# M040X.net
KiCad netlist of a schematic drawn in EAGLE
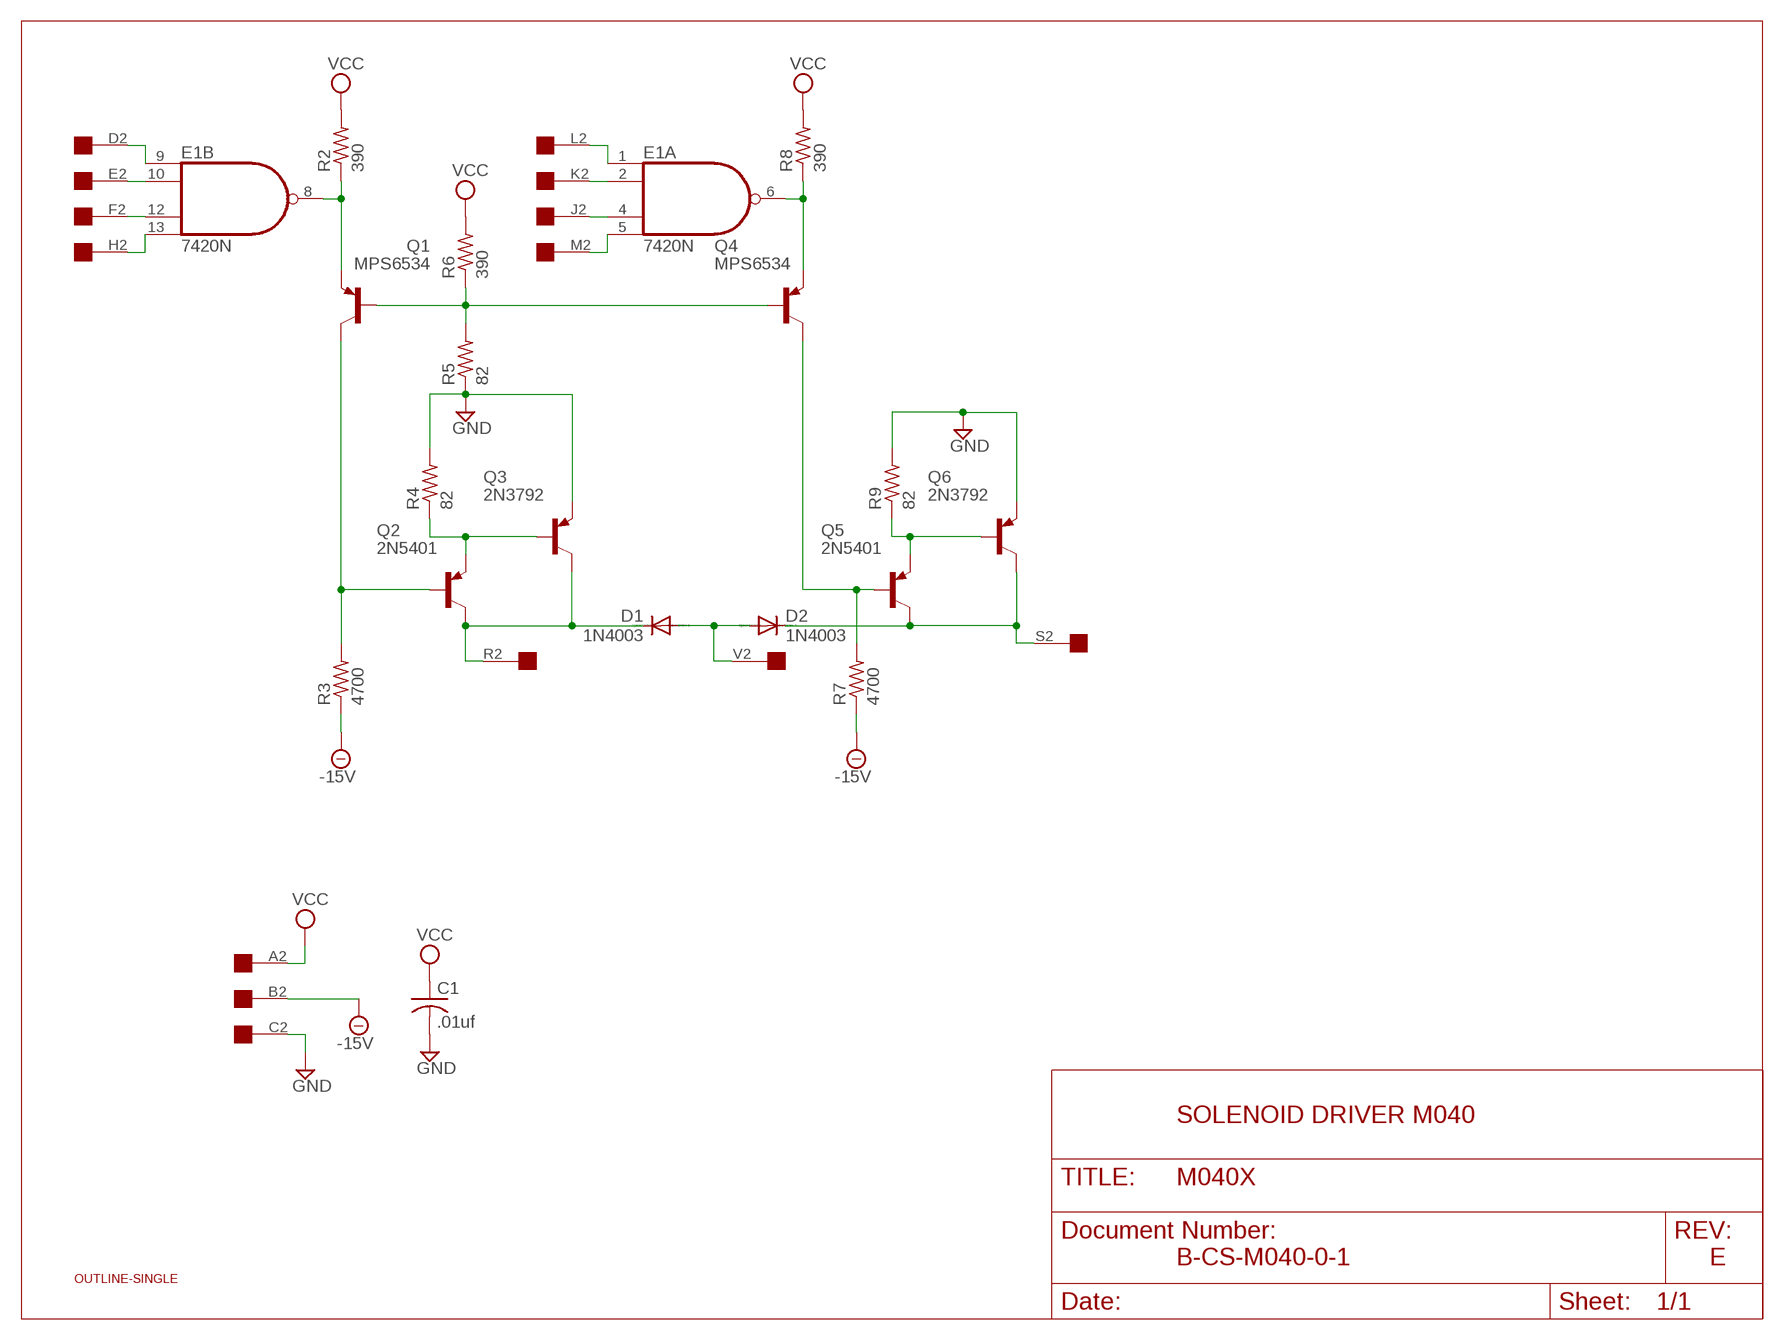
[diagram p0: schematic, sheet 1]

(export (version "E")
  (design (tool "Eeschema 10.0.6"))
  (components
    (comp (ref "C1")
      (value ".01uf")
      (footprint "eagle-import:C050-025X075")
      (libsource (lib "eagle-import") (part "C-US050-025X075"))
    )
    (comp (ref "D1")
      (value "1N4003")
      (footprint "eagle-import:DO41-10")
      (libsource (lib "eagle-import") (part "1N4004"))
    )
    (comp (ref "D2")
      (value "1N4003")
      (footprint "eagle-import:DO41-10")
      (libsource (lib "eagle-import") (part "1N4004"))
    )
    (comp (ref "E1")
      (value "7420N")
      (footprint "eagle-import:DIL14")
      (libsource (lib "eagle-import") (part "7420NS"))
    )
    (comp (ref "Q1")
      (value "MPS6534")
      (footprint "eagle-import:TO39")
      (libsource (lib "eagle-import") (part "-PNP-TO39-EBC2N2904"))
    )
    (comp (ref "Q2")
      (value "2N5401")
      (footprint "eagle-import:TO39")
      (libsource (lib "eagle-import") (part "-PNP-TO39-EBC2N2904"))
    )
    (comp (ref "Q3")
      (value "2N3792")
      (footprint "eagle-import:TO3")
      (libsource (lib "eagle-import") (part "-PNP-TO3"))
    )
    (comp (ref "Q4")
      (value "MPS6534")
      (footprint "eagle-import:TO39")
      (libsource (lib "eagle-import") (part "-PNP-TO39-EBC2N2904"))
    )
    (comp (ref "Q5")
      (value "2N5401")
      (footprint "eagle-import:TO39")
      (libsource (lib "eagle-import") (part "-PNP-TO39-EBC2N2904"))
    )
    (comp (ref "Q6")
      (value "2N3792")
      (footprint "eagle-import:TO3")
      (libsource (lib "eagle-import") (part "-PNP-TO3"))
    )
    (comp (ref "R2")
      (value "390")
      (footprint "eagle-import:0207_10")
      (libsource (lib "eagle-import") (part "R-US_0207/10"))
    )
    (comp (ref "R3")
      (value "4700")
      (footprint "eagle-import:0207_10")
      (libsource (lib "eagle-import") (part "R-US_0207/10"))
    )
    (comp (ref "R4")
      (value "82")
      (footprint "eagle-import:0207_10")
      (libsource (lib "eagle-import") (part "R-US_0207/10"))
    )
    (comp (ref "R5")
      (value "82")
      (footprint "eagle-import:0207_10")
      (libsource (lib "eagle-import") (part "R-US_0207/10"))
    )
    (comp (ref "R6")
      (value "390")
      (footprint "eagle-import:0207_10")
      (libsource (lib "eagle-import") (part "R-US_0207/10"))
    )
    (comp (ref "R7")
      (value "4700")
      (footprint "eagle-import:0207_10")
      (libsource (lib "eagle-import") (part "R-US_0207/10"))
    )
    (comp (ref "R8")
      (value "390")
      (footprint "eagle-import:0207_10")
      (libsource (lib "eagle-import") (part "R-US_0207/10"))
    )
    (comp (ref "R9")
      (value "82")
      (footprint "eagle-import:0207_10")
      (libsource (lib "eagle-import") (part "R-US_0207/10"))
    )
    (comp (ref "U$1")
      (value "OUTLINE-SINGLE")
      (footprint "eagle-import:SINGLE")
      (libsource (lib "eagle-import") (part "OUTLINE-SINGLE"))
    )
    (comp (ref "U$2")
      (value "EDGE-1")
      (footprint "eagle-import:EDGE-CON1")
      (libsource (lib "eagle-import") (part "EDGE-1"))
    )
  )
  (nets
    (net (code "1") (name "-15V") (class "Default")
      (node (ref "R3") (pin "1") (pinfunction "1_1") (pintype "passive"))
      (node (ref "R7") (pin "1") (pinfunction "1_1") (pintype "passive"))
      (node (ref "U$2") (pin "B2") (pinfunction "1_B2") (pintype "bidirectional"))
    )
    (net (code "2") (name "GND") (class "Default")
      (node (ref "C1") (pin "2") (pinfunction "2_2") (pintype "passive"))
      (node (ref "Q3") (pin "E") (pinfunction "E_E") (pintype "passive"))
      (node (ref "Q6") (pin "E") (pinfunction "E_E") (pintype "passive"))
      (node (ref "R4") (pin "2") (pinfunction "2_2") (pintype "passive"))
      (node (ref "R5") (pin "1") (pinfunction "1_1") (pintype "passive"))
      (node (ref "R9") (pin "2") (pinfunction "2_2") (pintype "passive"))
      (node (ref "U$2") (pin "C2") (pinfunction "1_C2") (pintype "bidirectional"))
    )
    (net (code "3") (name "Net-(E1A-I0)") (class "Default")
      (node (ref "E1") (pin "1") (pinfunction "I0_1") (pintype "input"))
      (node (ref "U$2") (pin "L2") (pinfunction "1_L2") (pintype "bidirectional"))
    )
    (net (code "4") (name "Net-(E1A-I1)") (class "Default")
      (node (ref "E1") (pin "2") (pinfunction "I1_2") (pintype "input"))
      (node (ref "U$2") (pin "K2") (pinfunction "1_K2") (pintype "bidirectional"))
    )
    (net (code "5") (name "Net-(E1A-I2)") (class "Default")
      (node (ref "E1") (pin "4") (pinfunction "I2_4") (pintype "input"))
      (node (ref "U$2") (pin "J2") (pinfunction "1_J2") (pintype "bidirectional"))
    )
    (net (code "6") (name "Net-(E1A-I3)") (class "Default")
      (node (ref "E1") (pin "5") (pinfunction "I3_5") (pintype "input"))
      (node (ref "U$2") (pin "M2") (pinfunction "1_M2") (pintype "bidirectional"))
    )
    (net (code "7") (name "Net-(E1A-O)") (class "Default")
      (node (ref "E1") (pin "6") (pinfunction "O_6") (pintype "output"))
      (node (ref "Q4") (pin "1") (pinfunction "E_1") (pintype "passive"))
      (node (ref "R8") (pin "1") (pinfunction "1_1") (pintype "passive"))
    )
    (net (code "8") (name "Net-(E1B-I0)") (class "Default")
      (node (ref "E1") (pin "9") (pinfunction "I0_9") (pintype "input"))
      (node (ref "U$2") (pin "D2") (pinfunction "1_D2") (pintype "bidirectional"))
    )
    (net (code "9") (name "Net-(E1B-I1)") (class "Default")
      (node (ref "E1") (pin "10") (pinfunction "I1_10") (pintype "input"))
      (node (ref "U$2") (pin "E2") (pinfunction "1_E2") (pintype "bidirectional"))
    )
    (net (code "10") (name "Net-(E1B-I2)") (class "Default")
      (node (ref "E1") (pin "12") (pinfunction "I2_12") (pintype "input"))
      (node (ref "U$2") (pin "F2") (pinfunction "1_F2") (pintype "bidirectional"))
    )
    (net (code "11") (name "Net-(E1B-I3)") (class "Default")
      (node (ref "E1") (pin "13") (pinfunction "I3_13") (pintype "input"))
      (node (ref "U$2") (pin "H2") (pinfunction "1_H2") (pintype "bidirectional"))
    )
    (net (code "12") (name "Net-(E1B-O)") (class "Default")
      (node (ref "E1") (pin "8") (pinfunction "O_8") (pintype "output"))
      (node (ref "Q1") (pin "1") (pinfunction "E_1") (pintype "passive"))
      (node (ref "R2") (pin "1") (pinfunction "1_1") (pintype "passive"))
    )
    (net (code "13") (name "Net-(Q1-B)") (class "Default")
      (node (ref "Q1") (pin "2") (pinfunction "B_2") (pintype "passive"))
      (node (ref "Q4") (pin "2") (pinfunction "B_2") (pintype "passive"))
      (node (ref "R5") (pin "2") (pinfunction "2_2") (pintype "passive"))
      (node (ref "R6") (pin "1") (pinfunction "1_1") (pintype "passive"))
    )
    (net (code "14") (name "Net-(Q1-C)") (class "Default")
      (node (ref "Q1") (pin "3") (pinfunction "C_3") (pintype "passive"))
      (node (ref "Q2") (pin "2") (pinfunction "B_2") (pintype "passive"))
      (node (ref "R3") (pin "2") (pinfunction "2_2") (pintype "passive"))
    )
    (net (code "15") (name "Net-(Q2-C)") (class "Default")
      (node (ref "D1") (pin "C") (pinfunction "C_C") (pintype "passive"))
      (node (ref "Q2") (pin "3") (pinfunction "C_3") (pintype "passive"))
      (node (ref "Q3") (pin "C") (pinfunction "C_C") (pintype "passive"))
      (node (ref "U$2") (pin "R2") (pinfunction "1_R2") (pintype "bidirectional"))
    )
    (net (code "16") (name "Net-(Q2-E)") (class "Default")
      (node (ref "Q2") (pin "1") (pinfunction "E_1") (pintype "passive"))
      (node (ref "Q3") (pin "B") (pinfunction "B_B") (pintype "passive"))
      (node (ref "R4") (pin "1") (pinfunction "1_1") (pintype "passive"))
    )
    (net (code "17") (name "Net-(Q4-C)") (class "Default")
      (node (ref "Q4") (pin "3") (pinfunction "C_3") (pintype "passive"))
      (node (ref "Q5") (pin "2") (pinfunction "B_2") (pintype "passive"))
      (node (ref "R7") (pin "2") (pinfunction "2_2") (pintype "passive"))
    )
    (net (code "18") (name "Net-(Q5-C)") (class "Default")
      (node (ref "D2") (pin "C") (pinfunction "C_C") (pintype "passive"))
      (node (ref "Q5") (pin "3") (pinfunction "C_3") (pintype "passive"))
      (node (ref "Q6") (pin "C") (pinfunction "C_C") (pintype "passive"))
      (node (ref "U$2") (pin "S2") (pinfunction "1_S2") (pintype "bidirectional"))
    )
    (net (code "19") (name "Net-(Q5-E)") (class "Default")
      (node (ref "Q5") (pin "1") (pinfunction "E_1") (pintype "passive"))
      (node (ref "Q6") (pin "B") (pinfunction "B_B") (pintype "passive"))
      (node (ref "R9") (pin "1") (pinfunction "1_1") (pintype "passive"))
    )
    (net (code "20") (name "Net-(U$2R-1)") (class "Default")
      (node (ref "D1") (pin "A") (pinfunction "A_A") (pintype "passive"))
      (node (ref "D2") (pin "A") (pinfunction "A_A") (pintype "passive"))
      (node (ref "U$2") (pin "V2") (pinfunction "1_V2") (pintype "bidirectional"))
    )
    (net (code "21") (name "VCC") (class "Default")
      (node (ref "C1") (pin "1") (pinfunction "1_1") (pintype "passive"))
      (node (ref "R2") (pin "2") (pinfunction "2_2") (pintype "passive"))
      (node (ref "R6") (pin "2") (pinfunction "2_2") (pintype "passive"))
      (node (ref "R8") (pin "2") (pinfunction "2_2") (pintype "passive"))
      (node (ref "U$2") (pin "A2") (pinfunction "1_A2") (pintype "bidirectional"))
    )
  )
)
